# IR.net
KiCad netlist of a schematic drawn in EAGLE
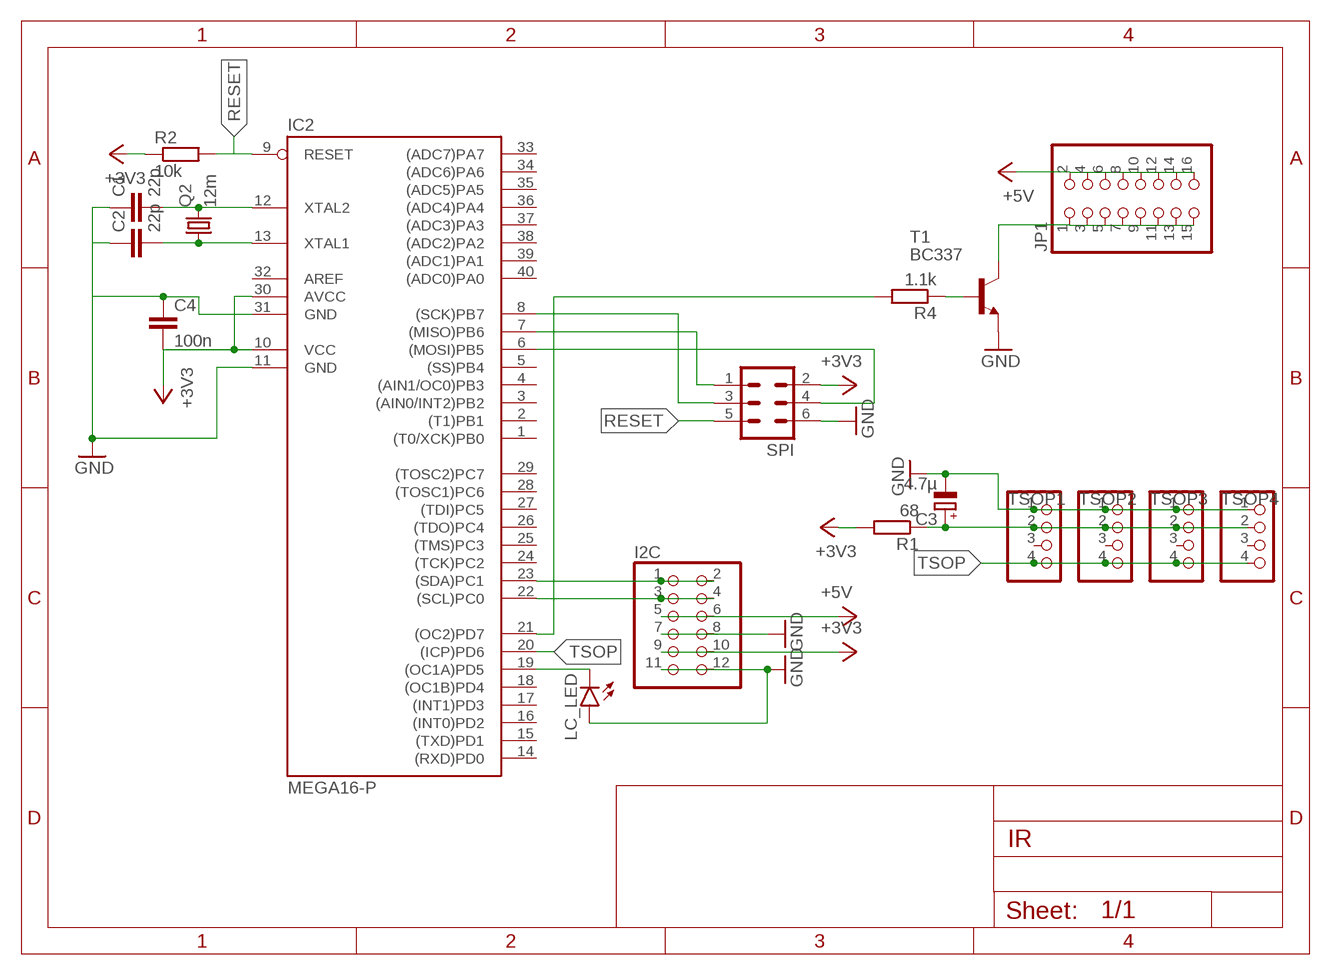
[diagram p0: schematic, sheet 1]

(export (version "E")
  (design (tool "Eeschema 10.0.6"))
  (components
    (comp (ref "C1")
      (value "22p")
      (footprint "eagle-import:C025-025X050")
      (libsource (lib "eagle-import") (part "C-EU025-025X050"))
    )
    (comp (ref "C2")
      (value "22p")
      (footprint "eagle-import:C025-025X050")
      (libsource (lib "eagle-import") (part "C-EU025-025X050"))
    )
    (comp (ref "C3")
      (value "4.7µ")
      (footprint "eagle-import:E1,8-4")
      (libsource (lib "eagle-import") (part "CPOL-EUE1.8-4"))
    )
    (comp (ref "C4")
      (value "100n")
      (footprint "eagle-import:C025-025X050")
      (libsource (lib "eagle-import") (part "C-EU025-025X050"))
    )
    (comp (ref "I2C")
      (value "PINHD-2X6")
      (footprint "eagle-import:2X06")
      (libsource (lib "eagle-import") (part "PINHD-2X6"))
    )
    (comp (ref "IC2")
      (value "MEGA16-P")
      (footprint "eagle-import:DIL40")
      (fields (field (name "MPN") "ATMEGA16-16PU"))
      (libsource (lib "eagle-import") (part "MEGA16-P"))
    )
    (comp (ref "JP1")
      (value "PINHD-2X8")
      (footprint "eagle-import:2X08")
      (libsource (lib "eagle-import") (part "PINHD-2X8"))
    )
    (comp (ref "LC_LED")
      (value "LED5MM")
      (footprint "eagle-import:LED5MM")
      (libsource (lib "eagle-import") (part "LED5MM"))
    )
    (comp (ref "Q2")
      (value "12m")
      (footprint "eagle-import:HC49_S")
      (libsource (lib "eagle-import") (part "CRYSTALHC49S"))
    )
    (comp (ref "R1")
      (value "68")
      (footprint "eagle-import:0207_7")
      (libsource (lib "eagle-import") (part "R-EU_0207/7"))
    )
    (comp (ref "R2")
      (value "10k")
      (footprint "eagle-import:0207_7")
      (libsource (lib "eagle-import") (part "R-EU_0207/7"))
    )
    (comp (ref "R4")
      (value "1.1k")
      (footprint "eagle-import:0207_7")
      (libsource (lib "eagle-import") (part "R-EU_0207/7"))
    )
    (comp (ref "SPI")
      (value "ML6")
      (footprint "eagle-import:ML6")
      (libsource (lib "eagle-import") (part "ML6"))
    )
    (comp (ref "T1")
      (value "BC337")
      (footprint "eagle-import:TO92")
      (libsource (lib "eagle-import") (part "BC337"))
    )
    (comp (ref "TSOP1")
      (value "PINHD-1X4")
      (footprint "eagle-import:1X04")
      (libsource (lib "eagle-import") (part "PINHD-1X4"))
    )
    (comp (ref "TSOP2")
      (value "PINHD-1X4")
      (footprint "eagle-import:1X04")
      (libsource (lib "eagle-import") (part "PINHD-1X4"))
    )
    (comp (ref "TSOP3")
      (value "PINHD-1X4")
      (footprint "eagle-import:1X04")
      (libsource (lib "eagle-import") (part "PINHD-1X4"))
    )
    (comp (ref "TSOP4")
      (value "PINHD-1X4")
      (footprint "eagle-import:1X04")
      (libsource (lib "eagle-import") (part "PINHD-1X4"))
    )
  )
  (nets
    (net (code "1") (name "+3V3") (class "Default")
      (node (ref "C4") (pin "2") (pinfunction "2_2") (pintype "passive"))
      (node (ref "I2C") (pin "10") (pinfunction "10_10") (pintype "passive"))
      (node (ref "I2C") (pin "9") (pinfunction "9_9") (pintype "passive"))
      (node (ref "IC2") (pin "10") (pinfunction "VCC_10") (pintype "power_in"))
      (node (ref "IC2") (pin "30") (pinfunction "AVCC_30") (pintype "power_in"))
      (node (ref "R1") (pin "2") (pinfunction "2_2") (pintype "passive"))
      (node (ref "R2") (pin "1") (pinfunction "1_1") (pintype "passive"))
      (node (ref "SPI") (pin "2") (pinfunction "2_2") (pintype "passive"))
    )
    (net (code "2") (name "+5V") (class "Default")
      (node (ref "I2C") (pin "5") (pinfunction "5_5") (pintype "passive"))
      (node (ref "I2C") (pin "6") (pinfunction "6_6") (pintype "passive"))
      (node (ref "JP1") (pin "10") (pinfunction "10_10") (pintype "passive"))
      (node (ref "JP1") (pin "12") (pinfunction "12_12") (pintype "passive"))
      (node (ref "JP1") (pin "14") (pinfunction "14_14") (pintype "passive"))
      (node (ref "JP1") (pin "16") (pinfunction "16_16") (pintype "passive"))
      (node (ref "JP1") (pin "2") (pinfunction "2_2") (pintype "passive"))
      (node (ref "JP1") (pin "4") (pinfunction "4_4") (pintype "passive"))
      (node (ref "JP1") (pin "6") (pinfunction "6_6") (pintype "passive"))
      (node (ref "JP1") (pin "8") (pinfunction "8_8") (pintype "passive"))
    )
    (net (code "3") (name "GND") (class "Default")
      (node (ref "C1") (pin "1") (pinfunction "1_1") (pintype "passive"))
      (node (ref "C2") (pin "1") (pinfunction "1_1") (pintype "passive"))
      (node (ref "C3") (pin "-") (pinfunction "-_-") (pintype "passive"))
      (node (ref "C4") (pin "1") (pinfunction "1_1") (pintype "passive"))
      (node (ref "I2C") (pin "11") (pinfunction "11_11") (pintype "passive"))
      (node (ref "I2C") (pin "12") (pinfunction "12_12") (pintype "passive"))
      (node (ref "I2C") (pin "7") (pinfunction "7_7") (pintype "passive"))
      (node (ref "I2C") (pin "8") (pinfunction "8_8") (pintype "passive"))
      (node (ref "IC2") (pin "11") (pinfunction "GND_11") (pintype "power_in"))
      (node (ref "IC2") (pin "31") (pinfunction "GND_31") (pintype "power_in"))
      (node (ref "LC_LED") (pin "A") (pinfunction "A_A") (pintype "passive"))
      (node (ref "SPI") (pin "6") (pinfunction "6_6") (pintype "passive"))
      (node (ref "T1") (pin "1") (pinfunction "E_1") (pintype "passive"))
      (node (ref "TSOP1") (pin "1") (pinfunction "1_1") (pintype "passive"))
      (node (ref "TSOP2") (pin "1") (pinfunction "1_1") (pintype "passive"))
      (node (ref "TSOP3") (pin "1") (pinfunction "1_1") (pintype "passive"))
      (node (ref "TSOP4") (pin "1") (pinfunction "1_1") (pintype "passive"))
    )
    (net (code "4") (name "Net-(C3-Pad+)") (class "Default")
      (node (ref "C3") (pin "+") (pinfunction "+_+") (pintype "passive"))
      (node (ref "R1") (pin "1") (pinfunction "1_1") (pintype "passive"))
      (node (ref "TSOP1") (pin "2") (pinfunction "2_2") (pintype "passive"))
      (node (ref "TSOP2") (pin "2") (pinfunction "2_2") (pintype "passive"))
      (node (ref "TSOP3") (pin "2") (pinfunction "2_2") (pintype "passive"))
      (node (ref "TSOP4") (pin "2") (pinfunction "2_2") (pintype "passive"))
    )
    (net (code "5") (name "Net-(IC2-(MISO)PB6)") (class "Default")
      (node (ref "IC2") (pin "7") (pinfunction "(MISO)PB6_7") (pintype "bidirectional"))
      (node (ref "SPI") (pin "1") (pinfunction "1_1") (pintype "passive"))
    )
    (net (code "6") (name "Net-(IC2-(MOSI)PB5)") (class "Default")
      (node (ref "IC2") (pin "6") (pinfunction "(MOSI)PB5_6") (pintype "bidirectional"))
      (node (ref "SPI") (pin "4") (pinfunction "4_4") (pintype "passive"))
    )
    (net (code "7") (name "Net-(IC2-(OC1A)PD5)") (class "Default")
      (node (ref "IC2") (pin "19") (pinfunction "(OC1A)PD5_19") (pintype "bidirectional"))
      (node (ref "LC_LED") (pin "K") (pinfunction "C_K") (pintype "passive"))
    )
    (net (code "8") (name "Net-(IC2-(OC2)PD7)") (class "Default")
      (node (ref "IC2") (pin "21") (pinfunction "(OC2)PD7_21") (pintype "bidirectional"))
      (node (ref "R4") (pin "2") (pinfunction "2_2") (pintype "passive"))
    )
    (net (code "9") (name "Net-(IC2-(SCK)PB7)") (class "Default")
      (node (ref "IC2") (pin "8") (pinfunction "(SCK)PB7_8") (pintype "bidirectional"))
      (node (ref "SPI") (pin "3") (pinfunction "3_3") (pintype "passive"))
    )
    (net (code "10") (name "Net-(IC2-(SCL)PC0)") (class "Default")
      (node (ref "I2C") (pin "3") (pinfunction "3_3") (pintype "passive"))
      (node (ref "I2C") (pin "4") (pinfunction "4_4") (pintype "passive"))
      (node (ref "IC2") (pin "22") (pinfunction "(SCL)PC0_22") (pintype "bidirectional"))
    )
    (net (code "11") (name "Net-(IC2-(SDA)PC1)") (class "Default")
      (node (ref "I2C") (pin "1") (pinfunction "1_1") (pintype "passive"))
      (node (ref "I2C") (pin "2") (pinfunction "2_2") (pintype "passive"))
      (node (ref "IC2") (pin "23") (pinfunction "(SDA)PC1_23") (pintype "bidirectional"))
    )
    (net (code "12") (name "Net-(IC2-XTAL1)") (class "Default")
      (node (ref "C2") (pin "2") (pinfunction "2_2") (pintype "passive"))
      (node (ref "IC2") (pin "13") (pinfunction "XTAL1_13") (pintype "bidirectional"))
      (node (ref "Q2") (pin "1") (pinfunction "1_1") (pintype "passive"))
    )
    (net (code "13") (name "Net-(IC2-XTAL2)") (class "Default")
      (node (ref "C1") (pin "2") (pinfunction "2_2") (pintype "passive"))
      (node (ref "IC2") (pin "12") (pinfunction "XTAL2_12") (pintype "bidirectional"))
      (node (ref "Q2") (pin "2") (pinfunction "2_2") (pintype "passive"))
    )
    (net (code "14") (name "Net-(T1-B)") (class "Default")
      (node (ref "R4") (pin "1") (pinfunction "1_1") (pintype "passive"))
      (node (ref "T1") (pin "2") (pinfunction "B_2") (pintype "passive"))
    )
    (net (code "15") (name "Net-(T1-C)") (class "Default")
      (node (ref "JP1") (pin "1") (pinfunction "1_1") (pintype "passive"))
      (node (ref "JP1") (pin "11") (pinfunction "11_11") (pintype "passive"))
      (node (ref "JP1") (pin "13") (pinfunction "13_13") (pintype "passive"))
      (node (ref "JP1") (pin "15") (pinfunction "15_15") (pintype "passive"))
      (node (ref "JP1") (pin "3") (pinfunction "3_3") (pintype "passive"))
      (node (ref "JP1") (pin "5") (pinfunction "5_5") (pintype "passive"))
      (node (ref "JP1") (pin "7") (pinfunction "7_7") (pintype "passive"))
      (node (ref "JP1") (pin "9") (pinfunction "9_9") (pintype "passive"))
      (node (ref "T1") (pin "3") (pinfunction "C_3") (pintype "passive"))
    )
    (net (code "16") (name "RESET") (class "Default")
      (node (ref "IC2") (pin "9") (pinfunction "RESET_9") (pintype "input"))
      (node (ref "R2") (pin "2") (pinfunction "2_2") (pintype "passive"))
      (node (ref "SPI") (pin "5") (pinfunction "5_5") (pintype "passive"))
    )
    (net (code "17") (name "TSOP") (class "Default")
      (node (ref "IC2") (pin "20") (pinfunction "(ICP)PD6_20") (pintype "bidirectional"))
      (node (ref "TSOP1") (pin "4") (pinfunction "4_4") (pintype "passive"))
      (node (ref "TSOP2") (pin "4") (pinfunction "4_4") (pintype "passive"))
      (node (ref "TSOP3") (pin "4") (pinfunction "4_4") (pintype "passive"))
      (node (ref "TSOP4") (pin "4") (pinfunction "4_4") (pintype "passive"))
    )
    (net (code "18") (name "unconnected-(IC2-(ADC0)PA0-Pad40)") (class "Default")
      (node (ref "IC2") (pin "40") (pinfunction "(ADC0)PA0_40") (pintype "bidirectional"))
    )
    (net (code "19") (name "unconnected-(IC2-(ADC1)PA1-Pad39)") (class "Default")
      (node (ref "IC2") (pin "39") (pinfunction "(ADC1)PA1_39") (pintype "bidirectional"))
    )
    (net (code "20") (name "unconnected-(IC2-(ADC2)PA2-Pad38)") (class "Default")
      (node (ref "IC2") (pin "38") (pinfunction "(ADC2)PA2_38") (pintype "bidirectional"))
    )
    (net (code "21") (name "unconnected-(IC2-(ADC3)PA3-Pad37)") (class "Default")
      (node (ref "IC2") (pin "37") (pinfunction "(ADC3)PA3_37") (pintype "bidirectional"))
    )
    (net (code "22") (name "unconnected-(IC2-(ADC4)PA4-Pad36)") (class "Default")
      (node (ref "IC2") (pin "36") (pinfunction "(ADC4)PA4_36") (pintype "bidirectional"))
    )
    (net (code "23") (name "unconnected-(IC2-(ADC5)PA5-Pad35)") (class "Default")
      (node (ref "IC2") (pin "35") (pinfunction "(ADC5)PA5_35") (pintype "bidirectional"))
    )
    (net (code "24") (name "unconnected-(IC2-(ADC6)PA6-Pad34)") (class "Default")
      (node (ref "IC2") (pin "34") (pinfunction "(ADC6)PA6_34") (pintype "bidirectional"))
    )
    (net (code "25") (name "unconnected-(IC2-(ADC7)PA7-Pad33)") (class "Default")
      (node (ref "IC2") (pin "33") (pinfunction "(ADC7)PA7_33") (pintype "bidirectional"))
    )
    (net (code "26") (name "unconnected-(IC2-(AIN0{slash}INT2)PB2-Pad3)") (class "Default")
      (node (ref "IC2") (pin "3") (pinfunction "(AIN0/INT2)PB2_3") (pintype "bidirectional"))
    )
    (net (code "27") (name "unconnected-(IC2-(AIN1{slash}OC0)PB3-Pad4)") (class "Default")
      (node (ref "IC2") (pin "4") (pinfunction "(AIN1/OC0)PB3_4") (pintype "bidirectional"))
    )
    (net (code "28") (name "unconnected-(IC2-(INT0)PD2-Pad16)") (class "Default")
      (node (ref "IC2") (pin "16") (pinfunction "(INT0)PD2_16") (pintype "bidirectional"))
    )
    (net (code "29") (name "unconnected-(IC2-(INT1)PD3-Pad17)") (class "Default")
      (node (ref "IC2") (pin "17") (pinfunction "(INT1)PD3_17") (pintype "bidirectional"))
    )
    (net (code "30") (name "unconnected-(IC2-(OC1B)PD4-Pad18)") (class "Default")
      (node (ref "IC2") (pin "18") (pinfunction "(OC1B)PD4_18") (pintype "bidirectional"))
    )
    (net (code "31") (name "unconnected-(IC2-(RXD)PD0-Pad14)") (class "Default")
      (node (ref "IC2") (pin "14") (pinfunction "(RXD)PD0_14") (pintype "bidirectional"))
    )
    (net (code "32") (name "unconnected-(IC2-(SS)PB4-Pad5)") (class "Default")
      (node (ref "IC2") (pin "5") (pinfunction "(SS)PB4_5") (pintype "bidirectional"))
    )
    (net (code "33") (name "unconnected-(IC2-(T0{slash}XCK)PB0-Pad1)") (class "Default")
      (node (ref "IC2") (pin "1") (pinfunction "(T0/XCK)PB0_1") (pintype "bidirectional"))
    )
    (net (code "34") (name "unconnected-(IC2-(T1)PB1-Pad2)") (class "Default")
      (node (ref "IC2") (pin "2") (pinfunction "(T1)PB1_2") (pintype "bidirectional"))
    )
    (net (code "35") (name "unconnected-(IC2-(TCK)PC2-Pad24)") (class "Default")
      (node (ref "IC2") (pin "24") (pinfunction "(TCK)PC2_24") (pintype "bidirectional"))
    )
    (net (code "36") (name "unconnected-(IC2-(TDI)PC5-Pad27)") (class "Default")
      (node (ref "IC2") (pin "27") (pinfunction "(TDI)PC5_27") (pintype "bidirectional"))
    )
    (net (code "37") (name "unconnected-(IC2-(TDO)PC4-Pad26)") (class "Default")
      (node (ref "IC2") (pin "26") (pinfunction "(TDO)PC4_26") (pintype "bidirectional"))
    )
    (net (code "38") (name "unconnected-(IC2-(TMS)PC3-Pad25)") (class "Default")
      (node (ref "IC2") (pin "25") (pinfunction "(TMS)PC3_25") (pintype "bidirectional"))
    )
    (net (code "39") (name "unconnected-(IC2-(TOSC1)PC6-Pad28)") (class "Default")
      (node (ref "IC2") (pin "28") (pinfunction "(TOSC1)PC6_28") (pintype "bidirectional"))
    )
    (net (code "40") (name "unconnected-(IC2-(TOSC2)PC7-Pad29)") (class "Default")
      (node (ref "IC2") (pin "29") (pinfunction "(TOSC2)PC7_29") (pintype "bidirectional"))
    )
    (net (code "41") (name "unconnected-(IC2-(TXD)PD1-Pad15)") (class "Default")
      (node (ref "IC2") (pin "15") (pinfunction "(TXD)PD1_15") (pintype "bidirectional"))
    )
    (net (code "42") (name "unconnected-(IC2-AREF-Pad32)") (class "Default")
      (node (ref "IC2") (pin "32") (pinfunction "AREF_32") (pintype "passive"))
    )
    (net (code "43") (name "unconnected-(TSOP1-Pad3)") (class "Default")
      (node (ref "TSOP1") (pin "3") (pinfunction "3_3") (pintype "passive"))
    )
    (net (code "44") (name "unconnected-(TSOP2-Pad3)") (class "Default")
      (node (ref "TSOP2") (pin "3") (pinfunction "3_3") (pintype "passive"))
    )
    (net (code "45") (name "unconnected-(TSOP3-Pad3)") (class "Default")
      (node (ref "TSOP3") (pin "3") (pinfunction "3_3") (pintype "passive"))
    )
    (net (code "46") (name "unconnected-(TSOP4-Pad3)") (class "Default")
      (node (ref "TSOP4") (pin "3") (pinfunction "3_3") (pintype "passive"))
    )
  )
)
